# 04_Z-WAVE.net
KiCad netlist of a schematic drawn in Altium Designer
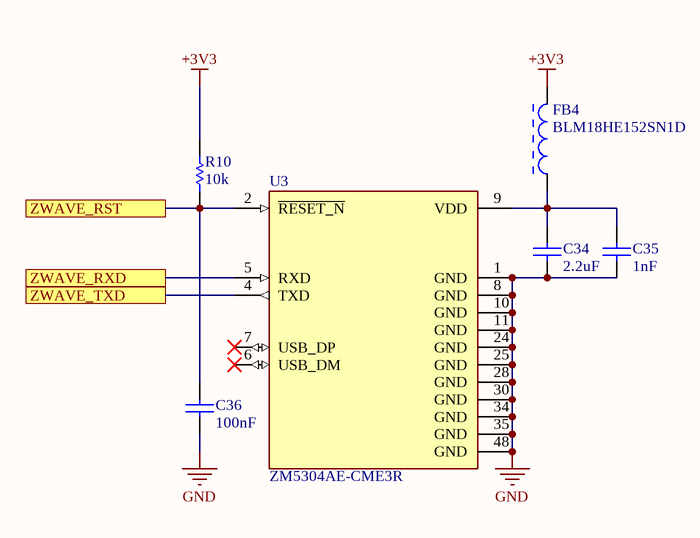
[diagram p0: 04. Z-WAVE.SchDoc]

(export (version "E")
  (design (tool "Eeschema 10.0.6"))
  (components
    (comp (ref "C34")
      (value "2.2uF")
      (footprint "CAPC1608X90X35NL10T15")
      (fields (field (name "MANUFACTURER") "Murata") (field (name "PART NUMBER") "GCM188R70J225KE22D"))
      (libsource (lib "Altium Content Vault") (part "CAP"))
    )
    (comp (ref "C35")
      (value "1nF")
      (footprint "CAPC1005X55X25NL05T10")
      (fields (field (name "PART NUMBER") "GRM1555C1H102JA01D") (field (name "MANUFACTURER") "Murata"))
      (libsource (lib "Altium Content Vault") (part "CAP"))
    )
    (comp (ref "C36")
      (value "100nF")
      (footprint "CAPC1005X56X25NL10T15")
      (fields
        (field (name "MANUFACTURER") "AVX Interconnect / Elco")
        (field (name "PART NUMBER") "04026D104KAT2A")
      )
      (libsource (lib "Altium Content Vault") (part "CAP"))
    )
    (comp (ref "FB4")
      (value "BLM18HE152SN1D")
      (footprint "MURA-BLM18-RF-H4-CHIP-2_V")
      (fields (field (name "MANUFACTURER") "Murata"))
      (libsource (lib "Altium Content Vault") (part "MURA-FB-2"))
    )
    (comp (ref "R10")
      (value "10k")
      (footprint "RESC1005X40X25NL05T05")
      (fields (field (name "MANUFACTURER") "Vishay Dale") (field (name "PART NUMBER") "CRCW040210K0FKED"))
      (libsource (lib "Altium Content Vault") (part "RES"))
    )
    (comp (ref "U3")
      (value "ZM5304AE-CME3R")
      (footprint "ZM5304AE-CME3R")
      (description "General ISM < 1GHz Z-WaveÂ® Transceiver Module 868MHz Surface Mount")
      (fields (field (name "MF") "Silicon Labs") (field (name "DIGI-KEY_PART_NUMBER") "703-1074-1-ND"))
      (libsource (lib "SyTungNguyen") (part "ZM5304AE-CME3R"))
    )
  )
  (nets
    (net (code "1") (name "+3V3") (class "Default")
      (node (ref "FB4") (pin "2") (pinfunction "2_2") (pintype "passive"))
      (node (ref "R10") (pin "2") (pinfunction "2_2") (pintype "passive"))
    )
    (net (code "2") (name "/ZWAVE_RST") (class "Default")
      (node (ref "C36") (pin "2") (pinfunction "2_2") (pintype "passive"))
      (node (ref "R10") (pin "1") (pinfunction "1_1") (pintype "passive"))
      (node (ref "U3") (pin "2") (pinfunction "~{RESET_N}_2") (pintype "input"))
    )
    (net (code "3") (name "/ZWAVE_RXD") (class "Default")
      (node (ref "U3") (pin "5") (pinfunction "RXD_5") (pintype "input"))
    )
    (net (code "4") (name "/ZWAVE_TXD") (class "Default")
      (node (ref "U3") (pin "4") (pinfunction "TXD_4") (pintype "output"))
    )
    (net (code "5") (name "GND") (class "Default")
      (node (ref "C34") (pin "1") (pinfunction "1_1") (pintype "passive"))
      (node (ref "C35") (pin "1") (pinfunction "1_1") (pintype "passive"))
      (node (ref "C36") (pin "1") (pinfunction "1_1") (pintype "passive"))
      (node (ref "U3") (pin "1") (pinfunction "GND_1") (pintype "power_in"))
      (node (ref "U3") (pin "10") (pinfunction "GND_10") (pintype "power_in"))
      (node (ref "U3") (pin "11") (pinfunction "GND_11") (pintype "power_in"))
      (node (ref "U3") (pin "24") (pinfunction "GND_24") (pintype "power_in"))
      (node (ref "U3") (pin "25") (pinfunction "GND_25") (pintype "power_in"))
      (node (ref "U3") (pin "28") (pinfunction "GND_28") (pintype "power_in"))
      (node (ref "U3") (pin "30") (pinfunction "GND_30") (pintype "power_in"))
      (node (ref "U3") (pin "34") (pinfunction "GND_34") (pintype "power_in"))
      (node (ref "U3") (pin "35") (pinfunction "GND_35") (pintype "power_in"))
      (node (ref "U3") (pin "48") (pinfunction "GND_48") (pintype "power_in"))
      (node (ref "U3") (pin "8") (pinfunction "GND_8") (pintype "power_in"))
    )
    (net (code "6") (name "Net-(U3-VDD)") (class "Default")
      (node (ref "C34") (pin "2") (pinfunction "2_2") (pintype "passive"))
      (node (ref "C35") (pin "2") (pinfunction "2_2") (pintype "passive"))
      (node (ref "FB4") (pin "1") (pinfunction "1_1") (pintype "passive"))
      (node (ref "U3") (pin "9") (pinfunction "VDD_9") (pintype "power_in"))
    )
    (net (code "7") (name "unconnected-(U3-USB_DM-Pad6)") (class "Default")
      (node (ref "U3") (pin "6") (pinfunction "USB_DM_6") (pintype "bidirectional+no_connect"))
    )
    (net (code "8") (name "unconnected-(U3-USB_DP-Pad7)") (class "Default")
      (node (ref "U3") (pin "7") (pinfunction "USB_DP_7") (pintype "bidirectional+no_connect"))
    )
  )
)
